# CPU.net
KiCad netlist of a schematic drawn in Altium Designer
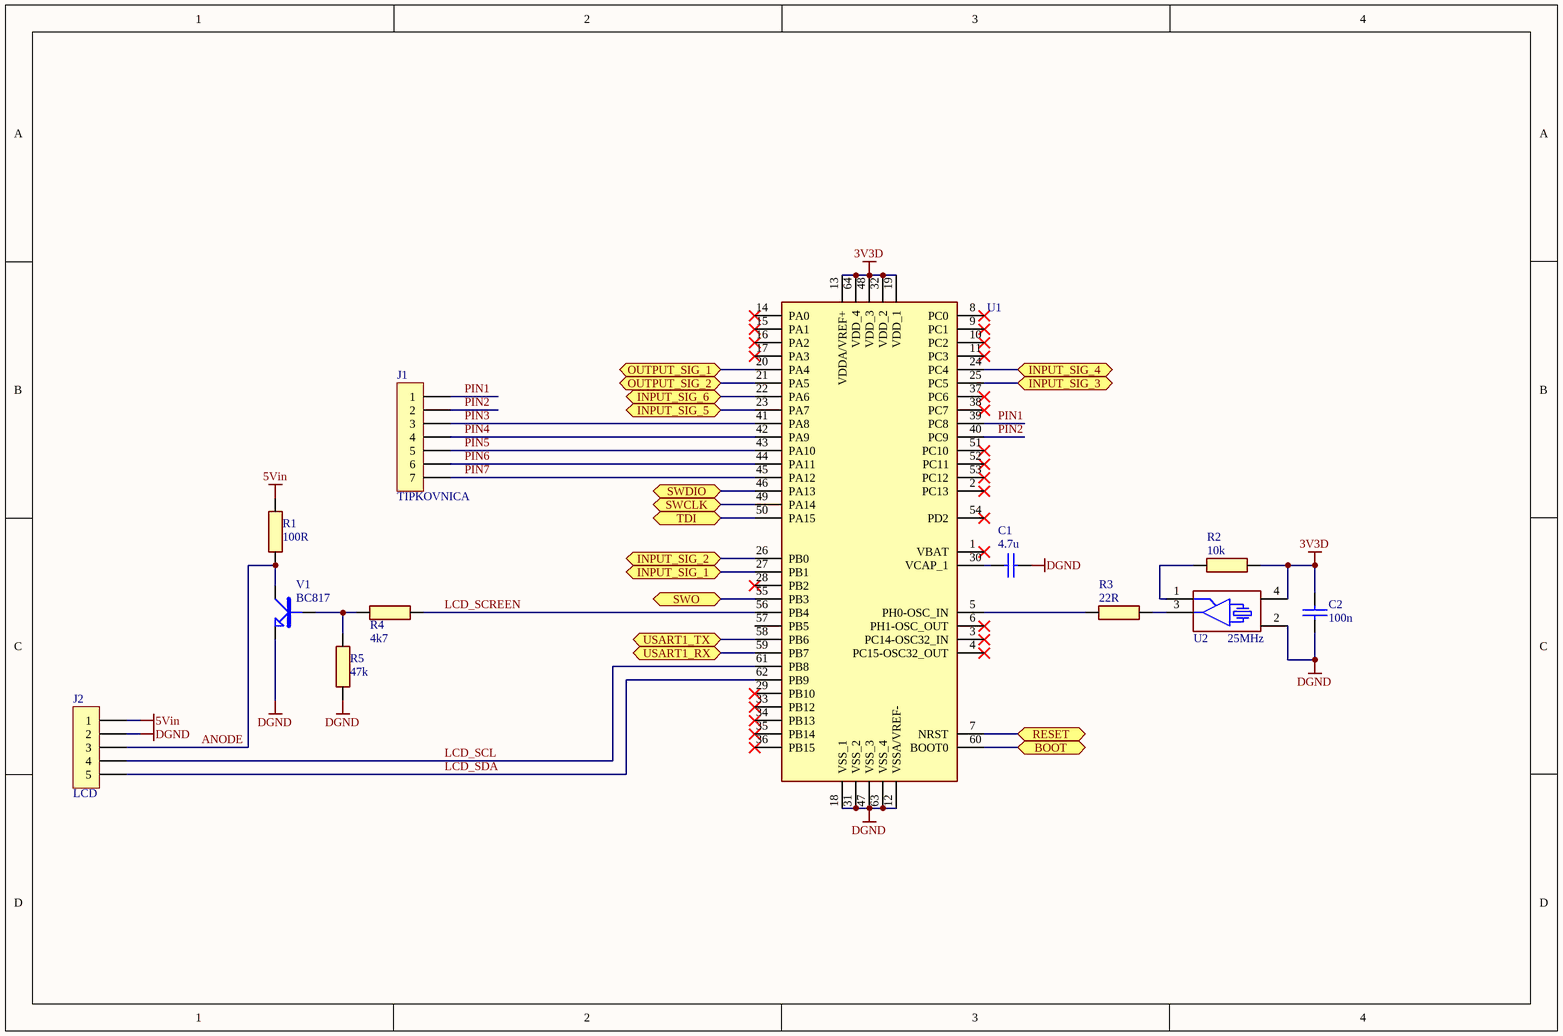
[diagram p0: CPU.SchDoc]

(export (version "E")
  (design (tool "Eeschema 10.0.6"))
  (components
    (comp (ref "C1")
      (value "4.7u")
      (footprint "CAP_0805_SMD")
      (description "0805")
      (libsource (lib "Moj_lib") (part "CAP"))
    )
    (comp (ref "C2")
      (value "100n")
      (footprint "CAP_0805_SMD")
      (description "0805")
      (libsource (lib "Moj_lib") (part "CAP"))
    )
    (comp (ref "J1")
      (value "TIPKOVNICA")
      (footprint "CON-SIP-7")
      (description "7 Pin connector")
      (libsource (lib "Moj_lib") (part "CON7"))
    )
    (comp (ref "J2")
      (value "LCD")
      (footprint "CON-SIP-5")
      (description "5 Pin connector")
      (libsource (lib "Moj_lib") (part "CON5"))
    )
    (comp (ref "R1")
      (value "100R")
      (footprint "RES_0805_SMD")
      (description "0805")
      (libsource (lib "Moj_lib") (part "RES"))
    )
    (comp (ref "R2")
      (value "10k")
      (footprint "RES_0805_SMD")
      (description "0805")
      (libsource (lib "") (part "RES_1"))
    )
    (comp (ref "R3")
      (value "22R")
      (footprint "RES_0805_SMD")
      (description "0805")
      (libsource (lib "") (part "RES_1"))
    )
    (comp (ref "R4")
      (value "4k7")
      (footprint "RES_0805_SMD")
      (description "0805")
      (libsource (lib "") (part "RES_2"))
    )
    (comp (ref "R5")
      (value "47k")
      (footprint "RES_0805_SMD")
      (description "0805")
      (libsource (lib "Moj_lib") (part "RES"))
    )
    (comp (ref "U1")
      (value "STM32F446RE")
      (footprint "STM32F446RE")
      (description "STM microcontroller")
      (libsource (lib "Moj_lib") (part "STM32F446RE"))
    )
    (comp (ref "U2")
      (value "25MHz")
      (footprint "AQ-7050")
      (description "Oscillator")
      (libsource (lib "Moj_lib") (part "OSCILATOR"))
    )
    (comp (ref "V1")
      (value "BC817")
      (footprint "SOT-23_P")
      (description "NPN tranzistor BC-817")
      (libsource (lib "ShemaLibrary_IEL") (part "BC817"))
    )
  )
  (nets
    (net (code "1") (name "/ANODE") (class "Default")
      (node (ref "J2") (pin "3") (pinfunction "3_3") (pintype "passive"))
      (node (ref "R1") (pin "1") (pinfunction "1_1") (pintype "passive"))
      (node (ref "V1") (pin "3") (pinfunction "C_3") (pintype "passive"))
    )
    (net (code "2") (name "/BOOT") (class "Default")
      (node (ref "U1") (pin "60") (pinfunction "BOOT0_60") (pintype "passive"))
    )
    (net (code "3") (name "/INPUT_SIG_1") (class "Default")
      (node (ref "U1") (pin "27") (pinfunction "PB1_27") (pintype "passive"))
    )
    (net (code "4") (name "/INPUT_SIG_2") (class "Default")
      (node (ref "U1") (pin "26") (pinfunction "PB0_26") (pintype "passive"))
    )
    (net (code "5") (name "/INPUT_SIG_3") (class "Default")
      (node (ref "U1") (pin "25") (pinfunction "PC5_25") (pintype "passive"))
    )
    (net (code "6") (name "/INPUT_SIG_4") (class "Default")
      (node (ref "U1") (pin "24") (pinfunction "PC4_24") (pintype "passive"))
    )
    (net (code "7") (name "/INPUT_SIG_5") (class "Default")
      (node (ref "U1") (pin "23") (pinfunction "PA7_23") (pintype "passive"))
    )
    (net (code "8") (name "/INPUT_SIG_6") (class "Default")
      (node (ref "U1") (pin "22") (pinfunction "PA6_22") (pintype "passive"))
    )
    (net (code "9") (name "/LCD_SCL") (class "Default")
      (node (ref "J2") (pin "4") (pinfunction "4_4") (pintype "passive"))
      (node (ref "U1") (pin "61") (pinfunction "PB8_61") (pintype "passive"))
    )
    (net (code "10") (name "/LCD_SCREEN") (class "Default")
      (node (ref "R4") (pin "2") (pinfunction "2_2") (pintype "passive"))
      (node (ref "U1") (pin "56") (pinfunction "PB4_56") (pintype "passive"))
    )
    (net (code "11") (name "/LCD_SDA") (class "Default")
      (node (ref "J2") (pin "5") (pinfunction "5_5") (pintype "passive"))
      (node (ref "U1") (pin "62") (pinfunction "PB9_62") (pintype "passive"))
    )
    (net (code "12") (name "/OUTPUT_SIG_1") (class "Default")
      (node (ref "U1") (pin "20") (pinfunction "PA4_20") (pintype "passive"))
    )
    (net (code "13") (name "/OUTPUT_SIG_2") (class "Default")
      (node (ref "U1") (pin "21") (pinfunction "PA5_21") (pintype "passive"))
    )
    (net (code "14") (name "/PIN1") (class "Default")
      (node (ref "J1") (pin "1") (pinfunction "1_1") (pintype "passive"))
      (node (ref "U1") (pin "39") (pinfunction "PC8_39") (pintype "passive"))
    )
    (net (code "15") (name "/PIN2") (class "Default")
      (node (ref "J1") (pin "2") (pinfunction "2_2") (pintype "passive"))
      (node (ref "U1") (pin "40") (pinfunction "PC9_40") (pintype "passive"))
    )
    (net (code "16") (name "/PIN3") (class "Default")
      (node (ref "J1") (pin "3") (pinfunction "3_3") (pintype "passive"))
      (node (ref "U1") (pin "41") (pinfunction "PA8_41") (pintype "passive"))
    )
    (net (code "17") (name "/PIN4") (class "Default")
      (node (ref "J1") (pin "4") (pinfunction "4_4") (pintype "passive"))
      (node (ref "U1") (pin "42") (pinfunction "PA9_42") (pintype "passive"))
    )
    (net (code "18") (name "/PIN5") (class "Default")
      (node (ref "J1") (pin "5") (pinfunction "5_5") (pintype "passive"))
      (node (ref "U1") (pin "43") (pinfunction "PA10_43") (pintype "passive"))
    )
    (net (code "19") (name "/PIN6") (class "Default")
      (node (ref "J1") (pin "6") (pinfunction "6_6") (pintype "passive"))
      (node (ref "U1") (pin "44") (pinfunction "PA11_44") (pintype "passive"))
    )
    (net (code "20") (name "/PIN7") (class "Default")
      (node (ref "J1") (pin "7") (pinfunction "7_7") (pintype "passive"))
      (node (ref "U1") (pin "45") (pinfunction "PA12_45") (pintype "passive"))
    )
    (net (code "21") (name "/RESET") (class "Default")
      (node (ref "U1") (pin "7") (pinfunction "NRST_7") (pintype "passive"))
    )
    (net (code "22") (name "/SWCLK") (class "Default")
      (node (ref "U1") (pin "49") (pinfunction "PA14_49") (pintype "passive"))
    )
    (net (code "23") (name "/SWDIO") (class "Default")
      (node (ref "U1") (pin "46") (pinfunction "PA13_46") (pintype "passive"))
    )
    (net (code "24") (name "/SWO") (class "Default")
      (node (ref "U1") (pin "55") (pinfunction "PB3_55") (pintype "passive"))
    )
    (net (code "25") (name "/TDI") (class "Default")
      (node (ref "U1") (pin "50") (pinfunction "PA15_50") (pintype "passive"))
    )
    (net (code "26") (name "/USART1_RX") (class "Default")
      (node (ref "U1") (pin "59") (pinfunction "PB7_59") (pintype "passive"))
    )
    (net (code "27") (name "/USART1_TX") (class "Default")
      (node (ref "U1") (pin "58") (pinfunction "PB6_58") (pintype "passive"))
    )
    (net (code "28") (name "3V3D") (class "Default")
      (node (ref "C2") (pin "2") (pinfunction "2_2") (pintype "passive"))
      (node (ref "R2") (pin "1") (pinfunction "1_1") (pintype "passive"))
      (node (ref "U1") (pin "13") (pinfunction "VDDA/VREF+_13") (pintype "passive"))
      (node (ref "U1") (pin "19") (pinfunction "VDD_1_19") (pintype "passive"))
      (node (ref "U1") (pin "32") (pinfunction "VDD_2_32") (pintype "passive"))
      (node (ref "U1") (pin "48") (pinfunction "VDD_3_48") (pintype "passive"))
      (node (ref "U1") (pin "64") (pinfunction "VDD_4_64") (pintype "passive"))
      (node (ref "U2") (pin "4") (pinfunction "Vcc_4") (pintype "passive"))
    )
    (net (code "29") (name "5Vin") (class "Default")
      (node (ref "J2") (pin "1") (pinfunction "1_1") (pintype "passive"))
      (node (ref "R1") (pin "2") (pinfunction "2_2") (pintype "passive"))
    )
    (net (code "30") (name "DGND") (class "Default")
      (node (ref "C1") (pin "2") (pinfunction "2_2") (pintype "passive"))
      (node (ref "C2") (pin "1") (pinfunction "1_1") (pintype "passive"))
      (node (ref "J2") (pin "2") (pinfunction "2_2") (pintype "passive"))
      (node (ref "R5") (pin "1") (pinfunction "1_1") (pintype "passive"))
      (node (ref "U1") (pin "12") (pinfunction "VSSA/VREF-_12") (pintype "passive"))
      (node (ref "U1") (pin "18") (pinfunction "VSS_1_18") (pintype "passive"))
      (node (ref "U1") (pin "31") (pinfunction "VSS_2_31") (pintype "passive"))
      (node (ref "U1") (pin "47") (pinfunction "VSS_3_47") (pintype "passive"))
      (node (ref "U1") (pin "63") (pinfunction "VSS_4_63") (pintype "passive"))
      (node (ref "U2") (pin "2") (pinfunction "DGND_2") (pintype "passive"))
      (node (ref "V1") (pin "2") (pinfunction "E_2") (pintype "passive"))
    )
    (net (code "31") (name "Net-(U1-PH0-OSC_IN)") (class "Default")
      (node (ref "R3") (pin "2") (pinfunction "2_2") (pintype "passive"))
      (node (ref "U1") (pin "5") (pinfunction "PH0-OSC_IN_5") (pintype "passive"))
    )
    (net (code "32") (name "Net-(U1-VCAP_1)") (class "Default")
      (node (ref "C1") (pin "1") (pinfunction "1_1") (pintype "passive"))
      (node (ref "U1") (pin "30") (pinfunction "VCAP_1_30") (pintype "passive"))
    )
    (net (code "33") (name "Net-(U2-Out)") (class "Default")
      (node (ref "R3") (pin "1") (pinfunction "1_1") (pintype "passive"))
      (node (ref "U2") (pin "3") (pinfunction "Out_3") (pintype "passive"))
    )
    (net (code "34") (name "Net-(U2-PV)") (class "Default")
      (node (ref "R2") (pin "2") (pinfunction "2_2") (pintype "passive"))
      (node (ref "U2") (pin "1") (pinfunction "PV_1") (pintype "passive"))
    )
    (net (code "35") (name "Net-(V1-B)") (class "Default")
      (node (ref "R4") (pin "1") (pinfunction "1_1") (pintype "passive"))
      (node (ref "R5") (pin "2") (pinfunction "2_2") (pintype "passive"))
      (node (ref "V1") (pin "1") (pinfunction "B_1") (pintype "passive"))
    )
    (net (code "36") (name "unconnected-(U1-PA0-Pad14)") (class "Default")
      (node (ref "U1") (pin "14") (pinfunction "PA0_14") (pintype "passive+no_connect"))
    )
    (net (code "37") (name "unconnected-(U1-PA1-Pad15)") (class "Default")
      (node (ref "U1") (pin "15") (pinfunction "PA1_15") (pintype "passive+no_connect"))
    )
    (net (code "38") (name "unconnected-(U1-PA2-Pad16)") (class "Default")
      (node (ref "U1") (pin "16") (pinfunction "PA2_16") (pintype "passive+no_connect"))
    )
    (net (code "39") (name "unconnected-(U1-PA3-Pad17)") (class "Default")
      (node (ref "U1") (pin "17") (pinfunction "PA3_17") (pintype "passive+no_connect"))
    )
    (net (code "40") (name "unconnected-(U1-PB2-Pad28)") (class "Default")
      (node (ref "U1") (pin "28") (pinfunction "PB2_28") (pintype "passive+no_connect"))
    )
    (net (code "41") (name "unconnected-(U1-PB5-Pad57)") (class "Default")
      (node (ref "U1") (pin "57") (pinfunction "PB5_57") (pintype "passive"))
    )
    (net (code "42") (name "unconnected-(U1-PB10-Pad29)") (class "Default")
      (node (ref "U1") (pin "29") (pinfunction "PB10_29") (pintype "passive+no_connect"))
    )
    (net (code "43") (name "unconnected-(U1-PB12-Pad33)") (class "Default")
      (node (ref "U1") (pin "33") (pinfunction "PB12_33") (pintype "passive+no_connect"))
    )
    (net (code "44") (name "unconnected-(U1-PB13-Pad34)") (class "Default")
      (node (ref "U1") (pin "34") (pinfunction "PB13_34") (pintype "passive+no_connect"))
    )
    (net (code "45") (name "unconnected-(U1-PB14-Pad35)") (class "Default")
      (node (ref "U1") (pin "35") (pinfunction "PB14_35") (pintype "passive+no_connect"))
    )
    (net (code "46") (name "unconnected-(U1-PB15-Pad36)") (class "Default")
      (node (ref "U1") (pin "36") (pinfunction "PB15_36") (pintype "passive+no_connect"))
    )
    (net (code "47") (name "unconnected-(U1-PC0-Pad8)") (class "Default")
      (node (ref "U1") (pin "8") (pinfunction "PC0_8") (pintype "passive+no_connect"))
    )
    (net (code "48") (name "unconnected-(U1-PC1-Pad9)") (class "Default")
      (node (ref "U1") (pin "9") (pinfunction "PC1_9") (pintype "passive+no_connect"))
    )
    (net (code "49") (name "unconnected-(U1-PC2-Pad10)") (class "Default")
      (node (ref "U1") (pin "10") (pinfunction "PC2_10") (pintype "passive+no_connect"))
    )
    (net (code "50") (name "unconnected-(U1-PC3-Pad11)") (class "Default")
      (node (ref "U1") (pin "11") (pinfunction "PC3_11") (pintype "passive+no_connect"))
    )
    (net (code "51") (name "unconnected-(U1-PC6-Pad37)") (class "Default")
      (node (ref "U1") (pin "37") (pinfunction "PC6_37") (pintype "passive+no_connect"))
    )
    (net (code "52") (name "unconnected-(U1-PC7-Pad38)") (class "Default")
      (node (ref "U1") (pin "38") (pinfunction "PC7_38") (pintype "passive+no_connect"))
    )
    (net (code "53") (name "unconnected-(U1-PC10-Pad51)") (class "Default")
      (node (ref "U1") (pin "51") (pinfunction "PC10_51") (pintype "passive+no_connect"))
    )
    (net (code "54") (name "unconnected-(U1-PC11-Pad52)") (class "Default")
      (node (ref "U1") (pin "52") (pinfunction "PC11_52") (pintype "passive+no_connect"))
    )
    (net (code "55") (name "unconnected-(U1-PC12-Pad53)") (class "Default")
      (node (ref "U1") (pin "53") (pinfunction "PC12_53") (pintype "passive+no_connect"))
    )
    (net (code "56") (name "unconnected-(U1-PC13-Pad2)") (class "Default")
      (node (ref "U1") (pin "2") (pinfunction "PC13_2") (pintype "passive+no_connect"))
    )
    (net (code "57") (name "unconnected-(U1-PC14-OSC32_IN-Pad3)") (class "Default")
      (node (ref "U1") (pin "3") (pinfunction "PC14-OSC32_IN_3") (pintype "passive+no_connect"))
    )
    (net (code "58") (name "unconnected-(U1-PC15-OSC32_OUT-Pad4)") (class "Default")
      (node (ref "U1") (pin "4") (pinfunction "PC15-OSC32_OUT_4") (pintype "passive+no_connect"))
    )
    (net (code "59") (name "unconnected-(U1-PD2-Pad54)") (class "Default")
      (node (ref "U1") (pin "54") (pinfunction "PD2_54") (pintype "passive+no_connect"))
    )
    (net (code "60") (name "unconnected-(U1-PH1-OSC_OUT-Pad6)") (class "Default")
      (node (ref "U1") (pin "6") (pinfunction "PH1-OSC_OUT_6") (pintype "passive+no_connect"))
    )
    (net (code "61") (name "unconnected-(U1-VBAT-Pad1)") (class "Default")
      (node (ref "U1") (pin "1") (pinfunction "VBAT_1") (pintype "passive+no_connect"))
    )
  )
)
